# CardV1.net
KiCad netlist of a schematic drawn in Altium Designer
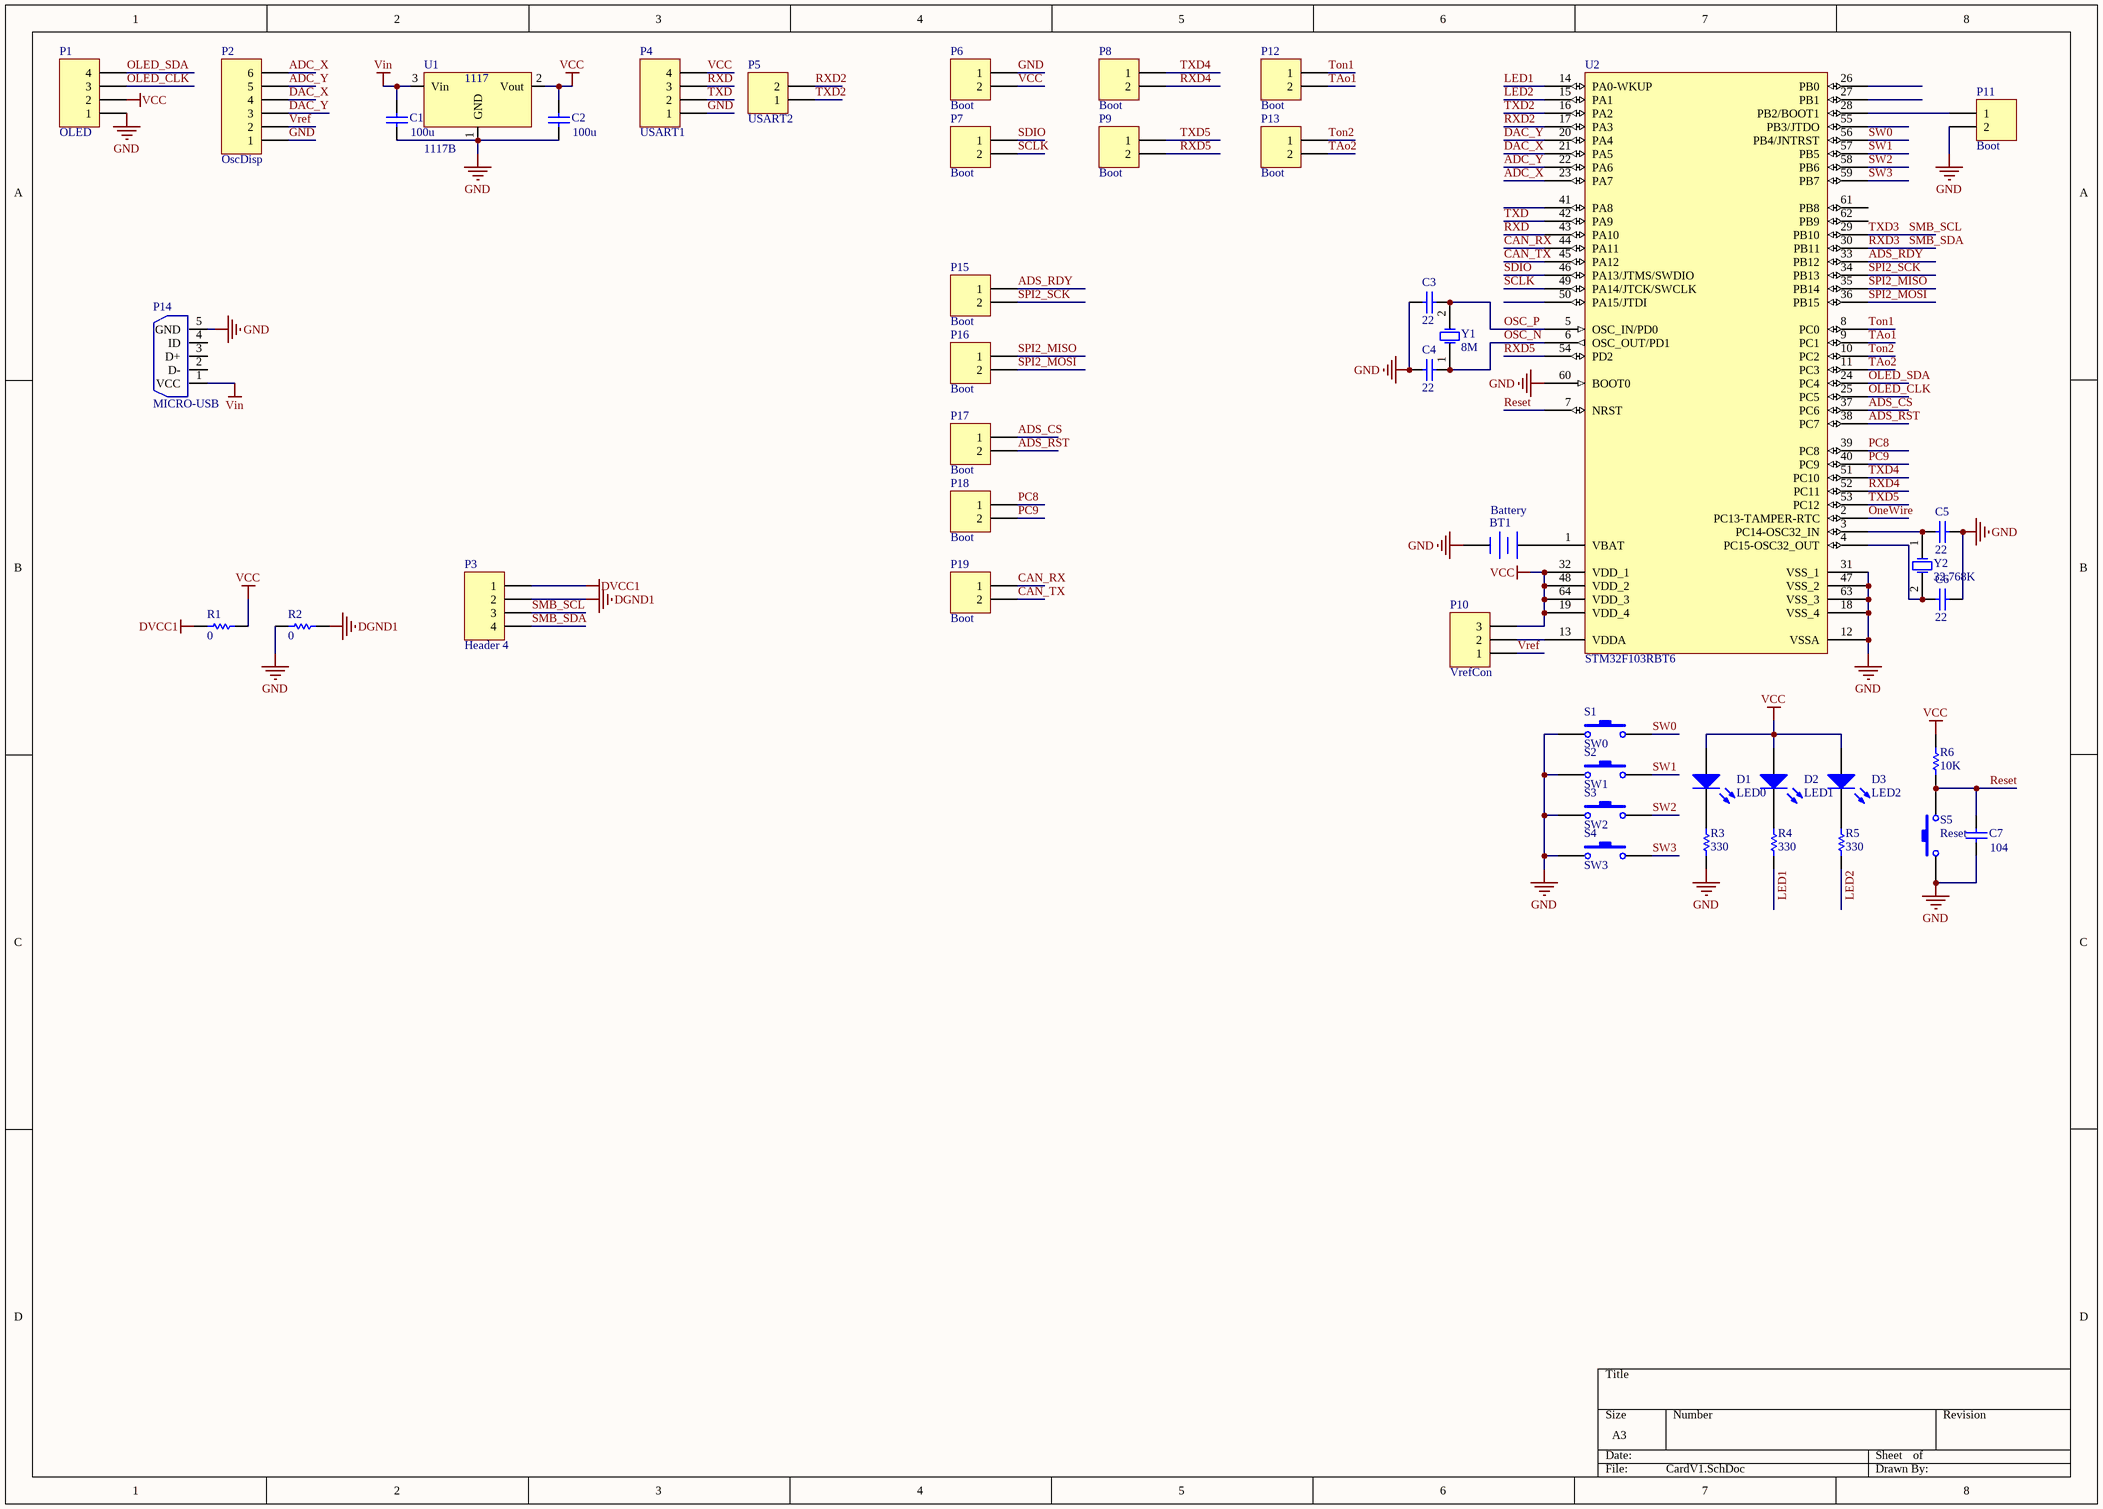
[diagram p0: CardV1.SchDoc]

(export (version "E")
  (design (tool "Eeschema 10.0.6"))
  (components
    (comp (ref "BT1")
      (value "Battery")
      (footprint "Battery-OneSide")
      (description "Multicell Battery")
      (fields (field (name "PUBLISHER") "Altium Limited"))
      (libsource (lib "Miscellaneous Devices") (part "Battery"))
    )
    (comp (ref "C1")
      (value "100u")
      (footprint "1608[0603]")
      (description "Capacitor")
      (fields (field (name "PUBLISHER") "Altium Limited"))
      (libsource (lib "Miscellaneous Devices") (part "Cap"))
    )
    (comp (ref "C2")
      (value "100u")
      (footprint "1608[0603]")
      (description "Capacitor")
      (fields (field (name "PUBLISHER") "Altium Limited"))
      (libsource (lib "Miscellaneous Devices") (part "Cap"))
    )
    (comp (ref "C3")
      (value "22")
      (footprint "1608[0603]")
      (description "Capacitor")
      (fields (field (name "PUBLISHER") "Altium Limited"))
      (libsource (lib "Miscellaneous Devices") (part "Cap"))
    )
    (comp (ref "C4")
      (value "22")
      (footprint "1608[0603]")
      (description "Capacitor")
      (fields (field (name "PUBLISHER") "Altium Limited"))
      (libsource (lib "Miscellaneous Devices") (part "Cap"))
    )
    (comp (ref "C5")
      (value "22")
      (footprint "1608[0603]")
      (description "Capacitor")
      (fields (field (name "PUBLISHER") "Altium Limited"))
      (libsource (lib "Miscellaneous Devices") (part "Cap"))
    )
    (comp (ref "C6")
      (value "22")
      (footprint "1608[0603]")
      (description "Capacitor")
      (fields (field (name "PUBLISHER") "Altium Limited"))
      (libsource (lib "Miscellaneous Devices") (part "Cap"))
    )
    (comp (ref "C7")
      (value "104")
      (footprint "3.2X1.6X1.1")
      (description "Capacitor")
      (fields (field (name "PUBLISHER") "Altium Limited"))
      (libsource (lib "Miscellaneous Devices") (part "Cap"))
    )
    (comp (ref "D1")
      (value "LED0")
      (footprint "SMDLED")
      (description "Typical INFRARED GaAs LED")
      (fields (field (name "PUBLISHER") "Altium Limited"))
      (libsource (lib "Miscellaneous Devices") (part "LED0"))
    )
    (comp (ref "D2")
      (value "LED1")
      (footprint "SMDLED")
      (description "Typical INFRARED GaAs LED")
      (fields (field (name "PUBLISHER") "Altium Limited"))
      (libsource (lib "Miscellaneous Devices") (part "LED0"))
    )
    (comp (ref "D3")
      (value "LED2")
      (footprint "SMDLED")
      (description "Typical INFRARED GaAs LED")
      (fields (field (name "PUBLISHER") "Altium Limited"))
      (libsource (lib "Miscellaneous Devices") (part "LED0"))
    )
    (comp (ref "P1")
      (value "OLED")
      (footprint "HDR1X4")
      (description "Header, 4-Pin")
      (fields (field (name "PUBLISHER") "Altium Limited"))
      (libsource (lib "Miscellaneous Connectors") (part "Header 4"))
    )
    (comp (ref "P2")
      (value "OscDisp")
      (footprint "Postage6")
      (description "Header, 6-Pin")
      (fields (field (name "PUBLISHER") "Altium Limited"))
      (libsource (lib "Miscellaneous Connectors") (part "Header 6"))
    )
    (comp (ref "P3")
      (value "Header 4")
      (footprint "HDR1X4")
      (description "Header, 4-Pin")
      (fields (field (name "PUBLISHER") "Altium Limited"))
      (libsource (lib "") (part "Header 4_1"))
    )
    (comp (ref "P4")
      (value "USART1")
      (footprint "Postage4")
      (description "Header, 4-Pin")
      (fields (field (name "PUBLISHER") "Altium Limited"))
      (libsource (lib "Miscellaneous Connectors") (part "Header 4"))
    )
    (comp (ref "P5")
      (value "USART2")
      (footprint "Postage2")
      (description "Header, 2-Pin")
      (fields (field (name "PUBLISHER") "Altium Limited"))
      (libsource (lib "") (part "Header 2_2"))
    )
    (comp (ref "P6")
      (value "Boot")
      (footprint "Switch2")
      (description "Header, 2-Pin")
      (fields (field (name "PUBLISHER") "Altium Limited"))
      (libsource (lib "Miscellaneous Connectors") (part "Header 2"))
    )
    (comp (ref "P7")
      (value "Boot")
      (footprint "Switch2")
      (description "Header, 2-Pin")
      (fields (field (name "PUBLISHER") "Altium Limited"))
      (libsource (lib "Miscellaneous Connectors") (part "Header 2"))
    )
    (comp (ref "P8")
      (value "Boot")
      (footprint "Switch2")
      (description "Header, 2-Pin")
      (fields (field (name "PUBLISHER") "Altium Limited"))
      (libsource (lib "Miscellaneous Connectors") (part "Header 2"))
    )
    (comp (ref "P9")
      (value "Boot")
      (footprint "Switch2")
      (description "Header, 2-Pin")
      (fields (field (name "PUBLISHER") "Altium Limited"))
      (libsource (lib "Miscellaneous Connectors") (part "Header 2"))
    )
    (comp (ref "P10")
      (value "VrefCon")
      (footprint "Switch3")
      (description "Header, 3-Pin")
      (fields (field (name "PUBLISHER") "Altium Limited"))
      (libsource (lib "Miscellaneous Connectors") (part "Header 3"))
    )
    (comp (ref "P11")
      (value "Boot")
      (footprint "Switch2")
      (description "Header, 2-Pin")
      (fields (field (name "PUBLISHER") "Altium Limited"))
      (libsource (lib "") (part "Header 2_1"))
    )
    (comp (ref "P12")
      (value "Boot")
      (footprint "Switch2")
      (description "Header, 2-Pin")
      (fields (field (name "PUBLISHER") "Altium Limited"))
      (libsource (lib "Miscellaneous Connectors") (part "Header 2"))
    )
    (comp (ref "P13")
      (value "Boot")
      (footprint "Switch2")
      (description "Header, 2-Pin")
      (fields (field (name "PUBLISHER") "Altium Limited"))
      (libsource (lib "Miscellaneous Connectors") (part "Header 2"))
    )
    (comp (ref "P14")
      (value "MICRO-USB")
      (footprint "MICRO_USB5P_SOP")
      (libsource (lib "MiniFly ") (part "USB5"))
    )
    (comp (ref "P15")
      (value "Boot")
      (footprint "Switch2")
      (description "Header, 2-Pin")
      (fields (field (name "PUBLISHER") "Altium Limited"))
      (libsource (lib "Miscellaneous Connectors") (part "Header 2"))
    )
    (comp (ref "P16")
      (value "Boot")
      (footprint "Switch2")
      (description "Header, 2-Pin")
      (fields (field (name "PUBLISHER") "Altium Limited"))
      (libsource (lib "Miscellaneous Connectors") (part "Header 2"))
    )
    (comp (ref "P17")
      (value "Boot")
      (footprint "Switch2")
      (description "Header, 2-Pin")
      (fields (field (name "PUBLISHER") "Altium Limited"))
      (libsource (lib "Miscellaneous Connectors") (part "Header 2"))
    )
    (comp (ref "P18")
      (value "Boot")
      (footprint "Switch2")
      (description "Header, 2-Pin")
      (fields (field (name "PUBLISHER") "Altium Limited"))
      (libsource (lib "Miscellaneous Connectors") (part "Header 2"))
    )
    (comp (ref "P19")
      (value "Boot")
      (footprint "Switch2")
      (description "Header, 2-Pin")
      (fields (field (name "PUBLISHER") "Altium Limited"))
      (libsource (lib "Miscellaneous Connectors") (part "Header 2"))
    )
    (comp (ref "R1")
      (value "0")
      (footprint "0603P")
      (description "Resistor")
      (fields (field (name "PUBLISHER") "Altium Limited"))
      (libsource (lib "Miscellaneous Devices") (part "Res1"))
    )
    (comp (ref "R2")
      (value "0")
      (footprint "0603P")
      (description "Resistor")
      (fields (field (name "PUBLISHER") "Altium Limited"))
      (libsource (lib "Miscellaneous Devices") (part "Res1"))
    )
    (comp (ref "R3")
      (value "330")
      (footprint "0603P")
      (description "Resistor")
      (fields (field (name "PUBLISHER") "Altium Limited"))
      (libsource (lib "Miscellaneous Devices") (part "Res1"))
    )
    (comp (ref "R4")
      (value "330")
      (footprint "0603P")
      (description "Resistor")
      (fields (field (name "PUBLISHER") "Altium Limited"))
      (libsource (lib "Miscellaneous Devices") (part "Res1"))
    )
    (comp (ref "R5")
      (value "330")
      (footprint "0603P")
      (description "Resistor")
      (fields (field (name "PUBLISHER") "Altium Limited"))
      (libsource (lib "Miscellaneous Devices") (part "Res1"))
    )
    (comp (ref "R6")
      (value "10K")
      (footprint "0603P")
      (description "Resistor")
      (fields (field (name "PUBLISHER") "Altium Limited"))
      (libsource (lib "Miscellaneous Devices") (part "Res1"))
    )
    (comp (ref "S1")
      (value "SW0")
      (footprint "Key")
      (description "Switch")
      (fields (field (name "PUBLISHER") "Altium Limited"))
      (libsource (lib "Miscellaneous Devices") (part "SW-PB"))
    )
    (comp (ref "S2")
      (value "SW1")
      (footprint "Key")
      (description "Switch")
      (fields (field (name "PUBLISHER") "Altium Limited"))
      (libsource (lib "Miscellaneous Devices") (part "SW-PB"))
    )
    (comp (ref "S3")
      (value "SW2")
      (footprint "Key")
      (description "Switch")
      (fields (field (name "PUBLISHER") "Altium Limited"))
      (libsource (lib "Miscellaneous Devices") (part "SW-PB"))
    )
    (comp (ref "S4")
      (value "SW3")
      (footprint "Key")
      (description "Switch")
      (fields (field (name "PUBLISHER") "Altium Limited"))
      (libsource (lib "Miscellaneous Devices") (part "SW-PB"))
    )
    (comp (ref "S5")
      (value "Reset")
      (footprint "Key")
      (description "Switch")
      (fields (field (name "PUBLISHER") "Altium Limited"))
      (libsource (lib "Miscellaneous Devices") (part "SW-PB"))
    )
    (comp (ref "U1") (value "1117B") (footprint "SOP-223") (libsource (lib "MISCESCH") (part "1117B")))
    (comp (ref "U2")
      (value "STM32F103RBT6")
      (footprint "LQFP64_N")
      (description "STM32 ARM-based 32-bit MCU with 128 Kbytes Flash, 64-pin LQFP, Industrial Temperature")
      (fields (field (name "PUBLISHER") "Altium Limited"))
      (libsource (lib "ST Microcontroller 32-Bit STM32") (part "STM32F103RBT6"))
    )
    (comp (ref "Y1")
      (value "8M")
      (footprint "R38")
      (description "Crystal Oscillator")
      (fields (field (name "PUBLISHER") "Altium Limited"))
      (libsource (lib "Miscellaneous Devices") (part "XTAL"))
    )
    (comp (ref "Y2")
      (value "32.768K")
      (footprint "R38")
      (description "Crystal Oscillator")
      (fields (field (name "PUBLISHER") "Altium Limited"))
      (libsource (lib "Miscellaneous Devices") (part "XTAL"))
    )
  )
  (nets
    (net (code "1") (name "/ADC_X") (class "Default")
      (node (ref "P2") (pin "6") (pinfunction "6_6") (pintype "passive"))
      (node (ref "U2") (pin "23") (pinfunction "PA7_23") (pintype "bidirectional"))
    )
    (net (code "2") (name "/ADC_Y") (class "Default")
      (node (ref "P2") (pin "5") (pinfunction "5_5") (pintype "passive"))
      (node (ref "U2") (pin "22") (pinfunction "PA6_22") (pintype "bidirectional"))
    )
    (net (code "3") (name "/ADS_CS") (class "Default")
      (node (ref "P17") (pin "1") (pinfunction "1_1") (pintype "passive"))
      (node (ref "U2") (pin "37") (pinfunction "PC6_37") (pintype "bidirectional"))
    )
    (net (code "4") (name "/ADS_RDY") (class "Default")
      (node (ref "P15") (pin "1") (pinfunction "1_1") (pintype "passive"))
      (node (ref "U2") (pin "33") (pinfunction "PB12_33") (pintype "bidirectional"))
    )
    (net (code "5") (name "/ADS_RST") (class "Default")
      (node (ref "P17") (pin "2") (pinfunction "2_2") (pintype "passive"))
      (node (ref "U2") (pin "38") (pinfunction "PC7_38") (pintype "bidirectional"))
    )
    (net (code "6") (name "/CAN_RX") (class "Default")
      (node (ref "P19") (pin "1") (pinfunction "1_1") (pintype "passive"))
      (node (ref "U2") (pin "44") (pinfunction "PA11_44") (pintype "bidirectional"))
    )
    (net (code "7") (name "/CAN_TX") (class "Default")
      (node (ref "P19") (pin "2") (pinfunction "2_2") (pintype "passive"))
      (node (ref "U2") (pin "45") (pinfunction "PA12_45") (pintype "bidirectional"))
    )
    (net (code "8") (name "/DAC_X") (class "Default")
      (node (ref "P2") (pin "4") (pinfunction "4_4") (pintype "passive"))
      (node (ref "U2") (pin "21") (pinfunction "PA5_21") (pintype "bidirectional"))
    )
    (net (code "9") (name "/DAC_Y") (class "Default")
      (node (ref "P2") (pin "3") (pinfunction "3_3") (pintype "passive"))
      (node (ref "U2") (pin "20") (pinfunction "PA4_20") (pintype "bidirectional"))
    )
    (net (code "10") (name "/LED1") (class "Default")
      (node (ref "R4") (pin "1") (pinfunction "1_1") (pintype "passive"))
      (node (ref "U2") (pin "14") (pinfunction "PA0-WKUP_14") (pintype "bidirectional"))
    )
    (net (code "11") (name "/LED2") (class "Default")
      (node (ref "R5") (pin "1") (pinfunction "1_1") (pintype "passive"))
      (node (ref "U2") (pin "15") (pinfunction "PA1_15") (pintype "bidirectional"))
    )
    (net (code "12") (name "/OLED_CLK") (class "Default")
      (node (ref "P1") (pin "3") (pinfunction "3_3") (pintype "passive"))
      (node (ref "U2") (pin "25") (pinfunction "PC5_25") (pintype "bidirectional"))
    )
    (net (code "13") (name "/OLED_SDA") (class "Default")
      (node (ref "P1") (pin "4") (pinfunction "4_4") (pintype "passive"))
      (node (ref "U2") (pin "24") (pinfunction "PC4_24") (pintype "bidirectional"))
    )
    (net (code "14") (name "/OSC_N") (class "Default")
      (node (ref "C4") (pin "2") (pinfunction "2_2") (pintype "passive"))
      (node (ref "U2") (pin "6") (pinfunction "OSC_OUT/PD1_6") (pintype "output"))
      (node (ref "Y1") (pin "1") (pinfunction "OSC1_1") (pintype "passive"))
    )
    (net (code "15") (name "/OSC_P") (class "Default")
      (node (ref "C3") (pin "1") (pinfunction "1_1") (pintype "passive"))
      (node (ref "U2") (pin "5") (pinfunction "OSC_IN/PD0_5") (pintype "input"))
      (node (ref "Y1") (pin "2") (pinfunction "OSC2_2") (pintype "passive"))
    )
    (net (code "16") (name "/OneWire") (class "Default")
      (node (ref "U2") (pin "2") (pinfunction "PC13-TAMPER-RTC_2") (pintype "bidirectional"))
    )
    (net (code "17") (name "/PC8") (class "Default")
      (node (ref "P18") (pin "1") (pinfunction "1_1") (pintype "passive"))
      (node (ref "U2") (pin "39") (pinfunction "PC8_39") (pintype "bidirectional"))
    )
    (net (code "18") (name "/PC9") (class "Default")
      (node (ref "P18") (pin "2") (pinfunction "2_2") (pintype "passive"))
      (node (ref "U2") (pin "40") (pinfunction "PC9_40") (pintype "bidirectional"))
    )
    (net (code "19") (name "/RXD") (class "Default")
      (node (ref "P4") (pin "3") (pinfunction "3_3") (pintype "passive"))
      (node (ref "U2") (pin "43") (pinfunction "PA10_43") (pintype "bidirectional"))
    )
    (net (code "20") (name "/RXD2") (class "Default")
      (node (ref "P5") (pin "2") (pinfunction "2_2") (pintype "passive"))
      (node (ref "U2") (pin "17") (pinfunction "PA3_17") (pintype "bidirectional"))
    )
    (net (code "21") (name "/RXD3") (class "Default")
      (node (ref "P3") (pin "4") (pinfunction "4_4") (pintype "passive"))
      (node (ref "U2") (pin "30") (pinfunction "PB11_30") (pintype "bidirectional"))
    )
    (net (code "22") (name "/RXD4") (class "Default")
      (node (ref "P8") (pin "2") (pinfunction "2_2") (pintype "passive"))
      (node (ref "U2") (pin "52") (pinfunction "PC11_52") (pintype "bidirectional"))
    )
    (net (code "23") (name "/RXD5") (class "Default")
      (node (ref "P9") (pin "2") (pinfunction "2_2") (pintype "passive"))
      (node (ref "U2") (pin "54") (pinfunction "PD2_54") (pintype "bidirectional"))
    )
    (net (code "24") (name "/Reset") (class "Default")
      (node (ref "C7") (pin "2") (pinfunction "2_2") (pintype "passive"))
      (node (ref "R6") (pin "1") (pinfunction "1_1") (pintype "passive"))
      (node (ref "S5") (pin "2") (pinfunction "2_2") (pintype "passive"))
      (node (ref "U2") (pin "7") (pinfunction "NRST_7") (pintype "bidirectional"))
    )
    (net (code "25") (name "/SCLK") (class "Default")
      (node (ref "P7") (pin "2") (pinfunction "2_2") (pintype "passive"))
      (node (ref "U2") (pin "49") (pinfunction "PA14/JTCK/SWCLK_49") (pintype "bidirectional"))
    )
    (net (code "26") (name "/SDIO") (class "Default")
      (node (ref "P7") (pin "1") (pinfunction "1_1") (pintype "passive"))
      (node (ref "U2") (pin "46") (pinfunction "PA13/JTMS/SWDIO_46") (pintype "bidirectional"))
    )
    (net (code "27") (name "/SMB_SCL") (class "Default")
      (node (ref "P3") (pin "3") (pinfunction "3_3") (pintype "passive"))
      (node (ref "U2") (pin "29") (pinfunction "PB10_29") (pintype "bidirectional"))
    )
    (net (code "28") (name "/SPI2_MISO") (class "Default")
      (node (ref "P16") (pin "1") (pinfunction "1_1") (pintype "passive"))
      (node (ref "U2") (pin "35") (pinfunction "PB14_35") (pintype "bidirectional"))
    )
    (net (code "29") (name "/SPI2_MOSI") (class "Default")
      (node (ref "P16") (pin "2") (pinfunction "2_2") (pintype "passive"))
      (node (ref "U2") (pin "36") (pinfunction "PB15_36") (pintype "bidirectional"))
    )
    (net (code "30") (name "/SPI2_SCK") (class "Default")
      (node (ref "P15") (pin "2") (pinfunction "2_2") (pintype "passive"))
      (node (ref "U2") (pin "34") (pinfunction "PB13_34") (pintype "bidirectional"))
    )
    (net (code "31") (name "/SW0") (class "Default")
      (node (ref "S1") (pin "2") (pinfunction "2_2") (pintype "passive"))
      (node (ref "U2") (pin "56") (pinfunction "PB4/JNTRST_56") (pintype "bidirectional"))
    )
    (net (code "32") (name "/SW1") (class "Default")
      (node (ref "S2") (pin "2") (pinfunction "2_2") (pintype "passive"))
      (node (ref "U2") (pin "57") (pinfunction "PB5_57") (pintype "bidirectional"))
    )
    (net (code "33") (name "/SW2") (class "Default")
      (node (ref "S3") (pin "2") (pinfunction "2_2") (pintype "passive"))
      (node (ref "U2") (pin "58") (pinfunction "PB6_58") (pintype "bidirectional"))
    )
    (net (code "34") (name "/SW3") (class "Default")
      (node (ref "S4") (pin "2") (pinfunction "2_2") (pintype "passive"))
      (node (ref "U2") (pin "59") (pinfunction "PB7_59") (pintype "bidirectional"))
    )
    (net (code "35") (name "/TAo1") (class "Default")
      (node (ref "P12") (pin "2") (pinfunction "2_2") (pintype "passive"))
      (node (ref "U2") (pin "9") (pinfunction "PC1_9") (pintype "bidirectional"))
    )
    (net (code "36") (name "/TAo2") (class "Default")
      (node (ref "P13") (pin "2") (pinfunction "2_2") (pintype "passive"))
      (node (ref "U2") (pin "11") (pinfunction "PC3_11") (pintype "bidirectional"))
    )
    (net (code "37") (name "/TXD") (class "Default")
      (node (ref "P4") (pin "2") (pinfunction "2_2") (pintype "passive"))
      (node (ref "U2") (pin "42") (pinfunction "PA9_42") (pintype "bidirectional"))
    )
    (net (code "38") (name "/TXD2") (class "Default")
      (node (ref "P5") (pin "1") (pinfunction "1_1") (pintype "passive"))
      (node (ref "U2") (pin "16") (pinfunction "PA2_16") (pintype "bidirectional"))
    )
    (net (code "39") (name "/TXD4") (class "Default")
      (node (ref "P8") (pin "1") (pinfunction "1_1") (pintype "passive"))
      (node (ref "U2") (pin "51") (pinfunction "PC10_51") (pintype "bidirectional"))
    )
    (net (code "40") (name "/TXD5") (class "Default")
      (node (ref "P9") (pin "1") (pinfunction "1_1") (pintype "passive"))
      (node (ref "U2") (pin "53") (pinfunction "PC12_53") (pintype "bidirectional"))
    )
    (net (code "41") (name "/Ton1") (class "Default")
      (node (ref "P12") (pin "1") (pinfunction "1_1") (pintype "passive"))
      (node (ref "U2") (pin "8") (pinfunction "PC0_8") (pintype "bidirectional"))
    )
    (net (code "42") (name "/Ton2") (class "Default")
      (node (ref "P13") (pin "1") (pinfunction "1_1") (pintype "passive"))
      (node (ref "U2") (pin "10") (pinfunction "PC2_10") (pintype "bidirectional"))
    )
    (net (code "43") (name "/Vref") (class "Default")
      (node (ref "P10") (pin "1") (pinfunction "1_1") (pintype "passive"))
      (node (ref "P2") (pin "2") (pinfunction "2_2") (pintype "passive"))
    )
    (net (code "44") (name "DGND1") (class "Default")
      (node (ref "P3") (pin "2") (pinfunction "2_2") (pintype "passive"))
      (node (ref "R2") (pin "2") (pinfunction "2_2") (pintype "passive"))
    )
    (net (code "45") (name "DVCC1") (class "Default")
      (node (ref "P3") (pin "1") (pinfunction "1_1") (pintype "passive"))
      (node (ref "R1") (pin "2") (pinfunction "2_2") (pintype "passive"))
    )
    (net (code "46") (name "GND") (class "Default")
      (node (ref "BT1") (pin "2") (pinfunction "-_2") (pintype "passive"))
      (node (ref "C1") (pin "1") (pinfunction "1_1") (pintype "passive"))
      (node (ref "C2") (pin "1") (pinfunction "1_1") (pintype "passive"))
      (node (ref "C3") (pin "2") (pinfunction "2_2") (pintype "passive"))
      (node (ref "C4") (pin "1") (pinfunction "1_1") (pintype "passive"))
      (node (ref "C5") (pin "2") (pinfunction "2_2") (pintype "passive"))
      (node (ref "C6") (pin "2") (pinfunction "2_2") (pintype "passive"))
      (node (ref "C7") (pin "1") (pinfunction "1_1") (pintype "passive"))
      (node (ref "P1") (pin "1") (pinfunction "1_1") (pintype "passive"))
      (node (ref "P11") (pin "2") (pinfunction "2_2") (pintype "passive"))
      (node (ref "P14") (pin "5") (pinfunction "GND_5") (pintype "passive"))
      (node (ref "P2") (pin "1") (pinfunction "1_1") (pintype "passive"))
      (node (ref "P4") (pin "1") (pinfunction "1_1") (pintype "passive"))
      (node (ref "P6") (pin "1") (pinfunction "1_1") (pintype "passive"))
      (node (ref "R2") (pin "1") (pinfunction "1_1") (pintype "passive"))
      (node (ref "R3") (pin "2") (pinfunction "2_2") (pintype "passive"))
      (node (ref "S1") (pin "1") (pinfunction "1_1") (pintype "passive"))
      (node (ref "S2") (pin "1") (pinfunction "1_1") (pintype "passive"))
      (node (ref "S3") (pin "1") (pinfunction "1_1") (pintype "passive"))
      (node (ref "S4") (pin "1") (pinfunction "1_1") (pintype "passive"))
      (node (ref "S5") (pin "1") (pinfunction "1_1") (pintype "passive"))
      (node (ref "U1") (pin "1") (pinfunction "GND_1") (pintype "passive"))
      (node (ref "U2") (pin "12") (pinfunction "VSSA_12") (pintype "power_in"))
      (node (ref "U2") (pin "18") (pinfunction "VSS_4_18") (pintype "power_in"))
      (node (ref "U2") (pin "31") (pinfunction "VSS_1_31") (pintype "power_in"))
      (node (ref "U2") (pin "47") (pinfunction "VSS_2_47") (pintype "power_in"))
      (node (ref "U2") (pin "60") (pinfunction "BOOT0_60") (pintype "input"))
      (node (ref "U2") (pin "63") (pinfunction "VSS_3_63") (pintype "power_in"))
    )
    (net (code "47") (name "Net-(BT1-+)") (class "Default")
      (node (ref "BT1") (pin "1") (pinfunction "+_1") (pintype "passive"))
      (node (ref "U2") (pin "1") (pinfunction "VBAT_1") (pintype "power_in"))
    )
    (net (code "48") (name "Net-(D1-K)") (class "Default")
      (node (ref "D1") (pin "2") (pinfunction "K_2") (pintype "passive"))
      (node (ref "R3") (pin "1") (pinfunction "1_1") (pintype "passive"))
    )
    (net (code "49") (name "Net-(D2-K)") (class "Default")
      (node (ref "D2") (pin "2") (pinfunction "K_2") (pintype "passive"))
      (node (ref "R4") (pin "2") (pinfunction "2_2") (pintype "passive"))
    )
    (net (code "50") (name "Net-(D3-K)") (class "Default")
      (node (ref "D3") (pin "2") (pinfunction "K_2") (pintype "passive"))
      (node (ref "R5") (pin "2") (pinfunction "2_2") (pintype "passive"))
    )
    (net (code "51") (name "Net-(U2-PB2{slash}BOOT1)") (class "Default")
      (node (ref "P11") (pin "1") (pinfunction "1_1") (pintype "passive"))
      (node (ref "U2") (pin "28") (pinfunction "PB2/BOOT1_28") (pintype "bidirectional"))
    )
    (net (code "52") (name "Net-(U2-PC14-OSC32_IN)") (class "Default")
      (node (ref "C5") (pin "1") (pinfunction "1_1") (pintype "passive"))
      (node (ref "U2") (pin "3") (pinfunction "PC14-OSC32_IN_3") (pintype "bidirectional"))
      (node (ref "Y2") (pin "1") (pinfunction "OSC1_1") (pintype "passive"))
    )
    (net (code "53") (name "Net-(U2-PC15-OSC32_OUT)") (class "Default")
      (node (ref "C6") (pin "1") (pinfunction "1_1") (pintype "passive"))
      (node (ref "U2") (pin "4") (pinfunction "PC15-OSC32_OUT_4") (pintype "bidirectional"))
      (node (ref "Y2") (pin "2") (pinfunction "OSC2_2") (pintype "passive"))
    )
    (net (code "54") (name "Net-(U2-VDDA)") (class "Default")
      (node (ref "P10") (pin "2") (pinfunction "2_2") (pintype "passive"))
      (node (ref "U2") (pin "13") (pinfunction "VDDA_13") (pintype "power_in"))
    )
    (net (code "55") (name "VCC") (class "Default")
      (node (ref "C2") (pin "2") (pinfunction "2_2") (pintype "passive"))
      (node (ref "D1") (pin "1") (pinfunction "A_1") (pintype "passive"))
      (node (ref "D2") (pin "1") (pinfunction "A_1") (pintype "passive"))
      (node (ref "D3") (pin "1") (pinfunction "A_1") (pintype "passive"))
      (node (ref "P1") (pin "2") (pinfunction "2_2") (pintype "passive"))
      (node (ref "P10") (pin "3") (pinfunction "3_3") (pintype "passive"))
      (node (ref "P4") (pin "4") (pinfunction "4_4") (pintype "passive"))
      (node (ref "P6") (pin "2") (pinfunction "2_2") (pintype "passive"))
      (node (ref "R1") (pin "1") (pinfunction "1_1") (pintype "passive"))
      (node (ref "R6") (pin "2") (pinfunction "2_2") (pintype "passive"))
      (node (ref "U1") (pin "2") (pinfunction "Vout_2") (pintype "passive"))
      (node (ref "U2") (pin "19") (pinfunction "VDD_4_19") (pintype "power_in"))
      (node (ref "U2") (pin "32") (pinfunction "VDD_1_32") (pintype "power_in"))
      (node (ref "U2") (pin "48") (pinfunction "VDD_2_48") (pintype "power_in"))
      (node (ref "U2") (pin "64") (pinfunction "VDD_3_64") (pintype "power_in"))
    )
    (net (code "56") (name "Vin") (class "Default")
      (node (ref "C1") (pin "2") (pinfunction "2_2") (pintype "passive"))
      (node (ref "P14") (pin "1") (pinfunction "VCC_1") (pintype "passive"))
      (node (ref "U1") (pin "3") (pinfunction "Vin_3") (pintype "passive"))
    )
    (net (code "57") (name "unconnected-(P14-D+-Pad3)") (class "Default")
      (node (ref "P14") (pin "3") (pinfunction "D+_3") (pintype "passive"))
    )
    (net (code "58") (name "unconnected-(P14-D--Pad2)") (class "Default")
      (node (ref "P14") (pin "2") (pinfunction "D-_2") (pintype "passive"))
    )
    (net (code "59") (name "unconnected-(P14-ID-Pad4)") (class "Default")
      (node (ref "P14") (pin "4") (pinfunction "ID_4") (pintype "passive"))
    )
    (net (code "60") (name "unconnected-(U2-PA8-Pad41)") (class "Default")
      (node (ref "U2") (pin "41") (pinfunction "PA8_41") (pintype "bidirectional"))
    )
    (net (code "61") (name "unconnected-(U2-PA15{slash}JTDI-Pad50)") (class "Default")
      (node (ref "U2") (pin "50") (pinfunction "PA15/JTDI_50") (pintype "bidirectional"))
    )
    (net (code "62") (name "unconnected-(U2-PB0-Pad26)") (class "Default")
      (node (ref "U2") (pin "26") (pinfunction "PB0_26") (pintype "bidirectional"))
    )
    (net (code "63") (name "unconnected-(U2-PB1-Pad27)") (class "Default")
      (node (ref "U2") (pin "27") (pinfunction "PB1_27") (pintype "bidirectional"))
    )
    (net (code "64") (name "unconnected-(U2-PB3{slash}JTDO-Pad55)") (class "Default")
      (node (ref "U2") (pin "55") (pinfunction "PB3/JTDO_55") (pintype "bidirectional"))
    )
    (net (code "65") (name "unconnected-(U2-PB8-Pad61)") (class "Default")
      (node (ref "U2") (pin "61") (pinfunction "PB8_61") (pintype "bidirectional"))
    )
    (net (code "66") (name "unconnected-(U2-PB9-Pad62)") (class "Default")
      (node (ref "U2") (pin "62") (pinfunction "PB9_62") (pintype "bidirectional"))
    )
  )
)
